# TIMESQUARE.net
KiCad netlist of a schematic drawn in EAGLE
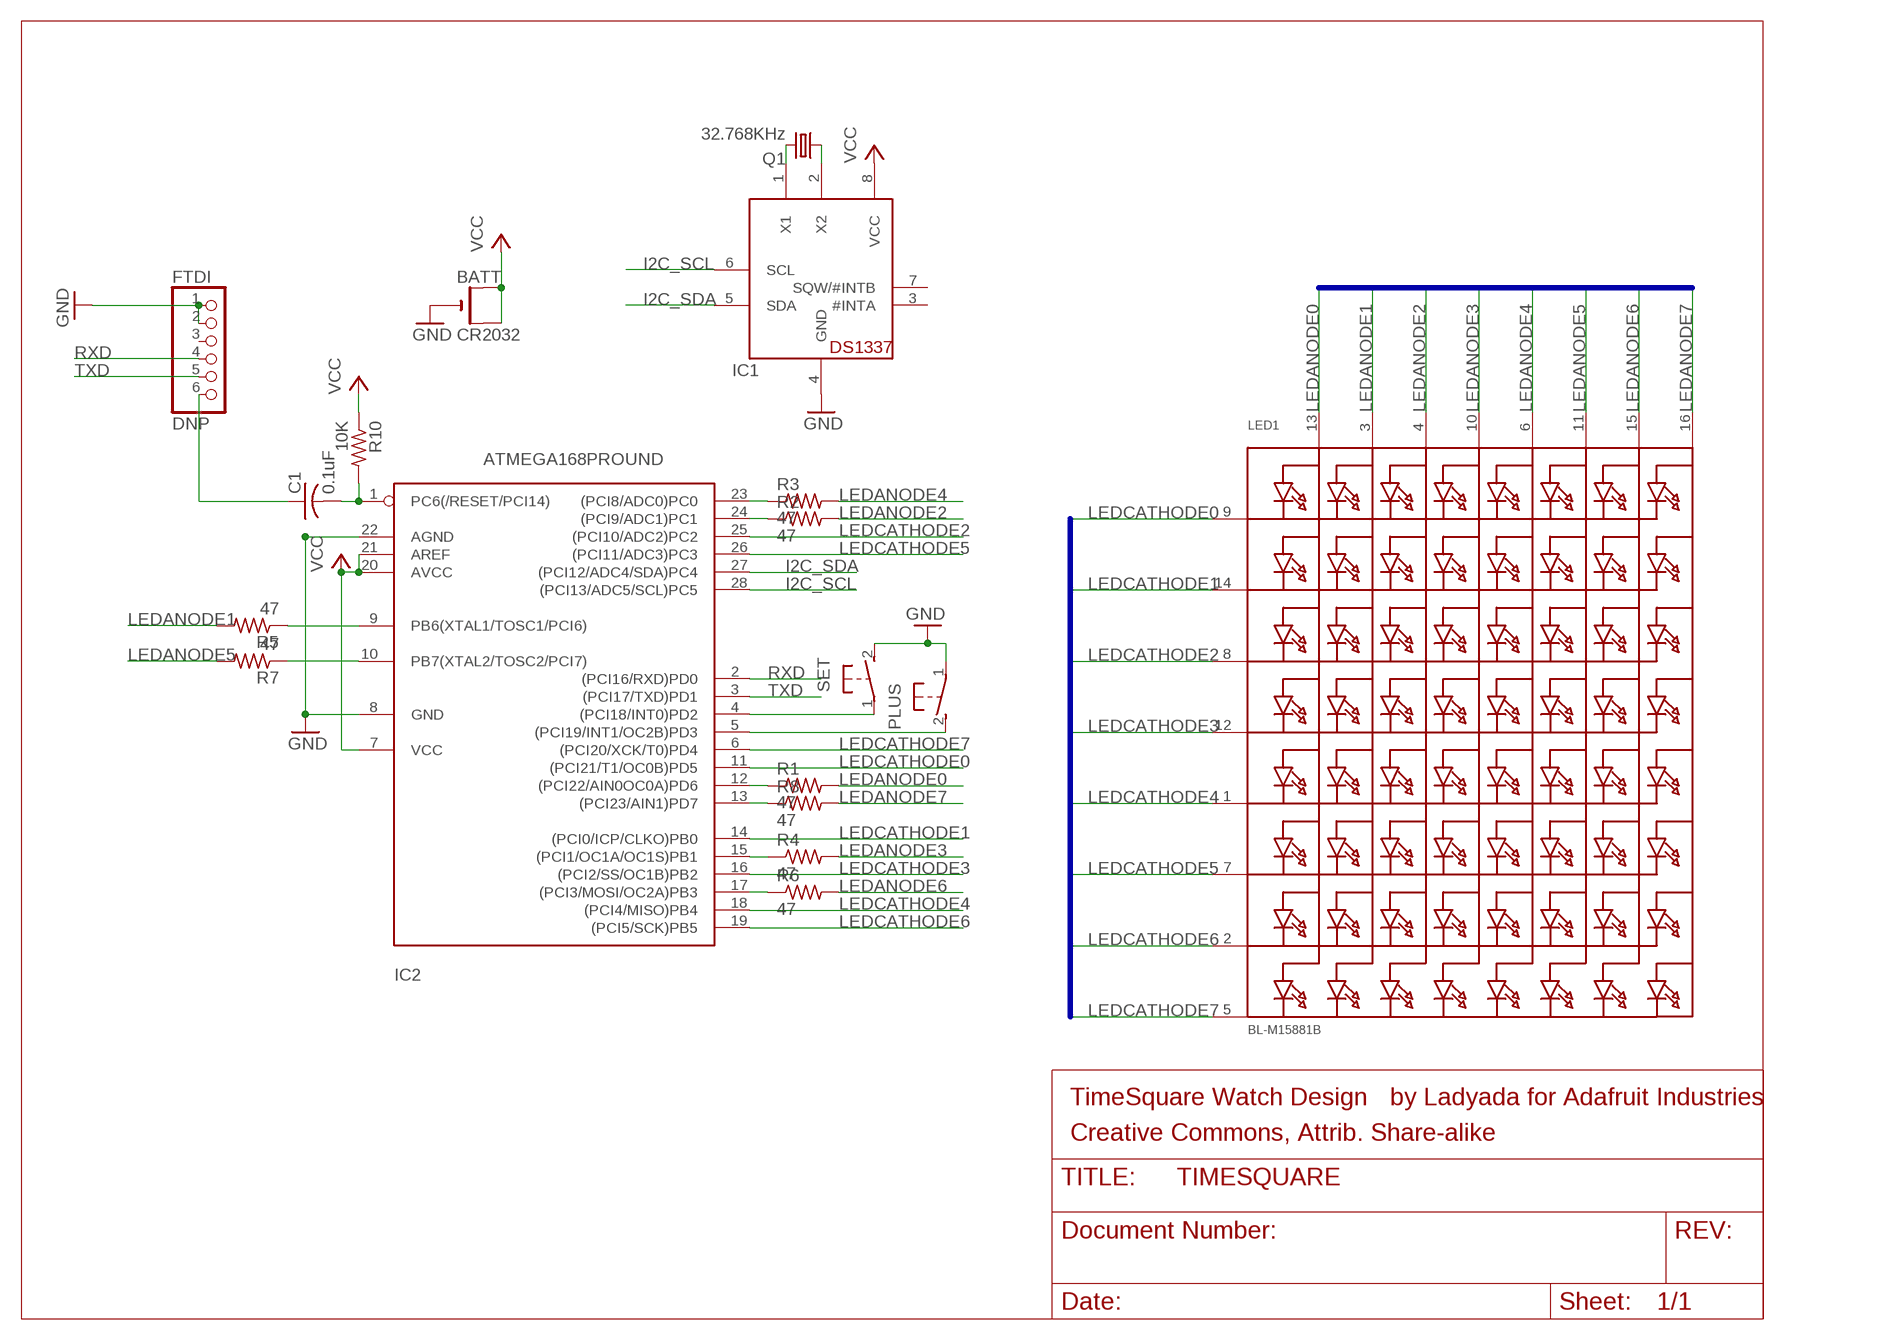
[diagram p0: schematic, sheet 1]

(export (version "E")
  (design (tool "Eeschema 10.0.6"))
  (components
    (comp (ref "BATT")
      (value "CR2032")
      (footprint "eagle-import:CR2032-THRU")
      (libsource (lib "eagle-import") (part "CR2032THM"))
    )
    (comp (ref "C1")
      (value "0.1uF")
      (footprint "eagle-import:C025-025X050")
      (libsource (lib "eagle-import") (part "C-US025-025X050"))
    )
    (comp (ref "FTDI")
      (value "DNP")
      (footprint "eagle-import:1X06-CLEAN")
      (libsource (lib "eagle-import") (part "PINHD-1X6CLEAN"))
    )
    (comp (ref "IC1")
      (value "DS1337")
      (footprint "eagle-import:DIL08-ROUND")
      (libsource (lib "eagle-import") (part "DS1337"))
    )
    (comp (ref "IC2")
      (value "ATMEGA168PROUND")
      (footprint "eagle-import:DIL28-3-ROUND")
      (libsource (lib "eagle-import") (part "ATMEGA168PROUND"))
    )
    (comp (ref "LED1")
      (value "BL-M15881B")
      (footprint "eagle-import:SEGMENT_BL-M15A881")
      (libsource (lib "eagle-import") (part "SEGMENT_8X8_ROWCATHODEBL-M15"))
    )
    (comp (ref "PLUS")
      (value "31-XXSKINNY")
      (footprint "eagle-import:B3F-31XX-SKINNIER")
      (libsource (lib "eagle-import") (part "31-XXSKINNY"))
    )
    (comp (ref "Q1")
      (value "32.768KHz")
      (footprint "eagle-import:TC38H")
      (libsource (lib "eagle-import") (part "CRYSTALTC38H"))
    )
    (comp (ref "R1")
      (value "47")
      (footprint "eagle-import:0204_7")
      (libsource (lib "eagle-import") (part "R-US_0204/7"))
    )
    (comp (ref "R2")
      (value "47")
      (footprint "eagle-import:0204_7")
      (libsource (lib "eagle-import") (part "R-US_0204/7"))
    )
    (comp (ref "R3")
      (value "47")
      (footprint "eagle-import:0204_7")
      (libsource (lib "eagle-import") (part "R-US_0204/7"))
    )
    (comp (ref "R4")
      (value "47")
      (footprint "eagle-import:0204_7")
      (libsource (lib "eagle-import") (part "R-US_0204/7"))
    )
    (comp (ref "R5")
      (value "47")
      (footprint "eagle-import:0204_7")
      (libsource (lib "eagle-import") (part "R-US_0204/7"))
    )
    (comp (ref "R6")
      (value "47")
      (footprint "eagle-import:0204_7")
      (libsource (lib "eagle-import") (part "R-US_0204/7"))
    )
    (comp (ref "R7")
      (value "47")
      (footprint "eagle-import:0204_7")
      (libsource (lib "eagle-import") (part "R-US_0204/7"))
    )
    (comp (ref "R8")
      (value "47")
      (footprint "eagle-import:0204_7")
      (libsource (lib "eagle-import") (part "R-US_0204/7"))
    )
    (comp (ref "R10")
      (value "10K")
      (footprint "eagle-import:0204_7")
      (libsource (lib "eagle-import") (part "R-US_0204/7"))
    )
    (comp (ref "SET")
      (value "31-XXSKINNY")
      (footprint "eagle-import:B3F-31XX-SKINNIER")
      (libsource (lib "eagle-import") (part "31-XXSKINNY"))
    )
  )
  (nets
    (net (code "1") (name "/I2C_SCL") (class "Default")
      (node (ref "IC1") (pin "6") (pinfunction "SCL_6") (pintype "bidirectional"))
      (node (ref "IC2") (pin "28") (pinfunction "(PCI13/ADC5/SCL)PC5_28") (pintype "bidirectional"))
    )
    (net (code "2") (name "/I2C_SDA") (class "Default")
      (node (ref "IC1") (pin "5") (pinfunction "SDA_5") (pintype "bidirectional"))
      (node (ref "IC2") (pin "27") (pinfunction "(PCI12/ADC4/SDA)PC4_27") (pintype "bidirectional"))
    )
    (net (code "3") (name "/LEDANODE0") (class "Default")
      (node (ref "LED1") (pin "13") (pinfunction "A1_13") (pintype "bidirectional"))
      (node (ref "R1") (pin "2") (pinfunction "2_2") (pintype "passive"))
    )
    (net (code "4") (name "/LEDANODE1") (class "Default")
      (node (ref "LED1") (pin "3") (pinfunction "A2_3") (pintype "bidirectional"))
      (node (ref "R5") (pin "2") (pinfunction "2_2") (pintype "passive"))
    )
    (net (code "5") (name "/LEDANODE2") (class "Default")
      (node (ref "LED1") (pin "4") (pinfunction "A3_4") (pintype "bidirectional"))
      (node (ref "R2") (pin "2") (pinfunction "2_2") (pintype "passive"))
    )
    (net (code "6") (name "/LEDANODE3") (class "Default")
      (node (ref "LED1") (pin "10") (pinfunction "A4_10") (pintype "bidirectional"))
      (node (ref "R4") (pin "2") (pinfunction "2_2") (pintype "passive"))
    )
    (net (code "7") (name "/LEDANODE4") (class "Default")
      (node (ref "LED1") (pin "6") (pinfunction "A5_6") (pintype "bidirectional"))
      (node (ref "R3") (pin "2") (pinfunction "2_2") (pintype "passive"))
    )
    (net (code "8") (name "/LEDANODE5") (class "Default")
      (node (ref "LED1") (pin "11") (pinfunction "A6_11") (pintype "bidirectional"))
      (node (ref "R7") (pin "2") (pinfunction "2_2") (pintype "passive"))
    )
    (net (code "9") (name "/LEDANODE6") (class "Default")
      (node (ref "LED1") (pin "15") (pinfunction "A7_15") (pintype "bidirectional"))
      (node (ref "R6") (pin "2") (pinfunction "2_2") (pintype "passive"))
    )
    (net (code "10") (name "/LEDANODE7") (class "Default")
      (node (ref "LED1") (pin "16") (pinfunction "A8_16") (pintype "bidirectional"))
      (node (ref "R8") (pin "2") (pinfunction "2_2") (pintype "passive"))
    )
    (net (code "11") (name "/LEDCATHODE0") (class "Default")
      (node (ref "IC2") (pin "11") (pinfunction "(PCI21/T1/OC0B)PD5_11") (pintype "bidirectional"))
      (node (ref "LED1") (pin "9") (pinfunction "K1_9") (pintype "bidirectional"))
    )
    (net (code "12") (name "/LEDCATHODE1") (class "Default")
      (node (ref "IC2") (pin "14") (pinfunction "(PCI0/ICP/CLKO)PB0_14") (pintype "bidirectional"))
      (node (ref "LED1") (pin "14") (pinfunction "K2_14") (pintype "bidirectional"))
    )
    (net (code "13") (name "/LEDCATHODE2") (class "Default")
      (node (ref "IC2") (pin "25") (pinfunction "(PCI10/ADC2)PC2_25") (pintype "bidirectional"))
      (node (ref "LED1") (pin "8") (pinfunction "K3_8") (pintype "bidirectional"))
    )
    (net (code "14") (name "/LEDCATHODE3") (class "Default")
      (node (ref "IC2") (pin "16") (pinfunction "(PCI2/SS/OC1B)PB2_16") (pintype "bidirectional"))
      (node (ref "LED1") (pin "12") (pinfunction "K4_12") (pintype "bidirectional"))
    )
    (net (code "15") (name "/LEDCATHODE4") (class "Default")
      (node (ref "IC2") (pin "18") (pinfunction "(PCI4/MISO)PB4_18") (pintype "bidirectional"))
      (node (ref "LED1") (pin "1") (pinfunction "K5_1") (pintype "bidirectional"))
    )
    (net (code "16") (name "/LEDCATHODE5") (class "Default")
      (node (ref "IC2") (pin "26") (pinfunction "(PCI11/ADC3)PC3_26") (pintype "bidirectional"))
      (node (ref "LED1") (pin "7") (pinfunction "K6_7") (pintype "bidirectional"))
    )
    (net (code "17") (name "/LEDCATHODE6") (class "Default")
      (node (ref "IC2") (pin "19") (pinfunction "(PCI5/SCK)PB5_19") (pintype "bidirectional"))
      (node (ref "LED1") (pin "2") (pinfunction "K7_2") (pintype "bidirectional"))
    )
    (net (code "18") (name "/LEDCATHODE7") (class "Default")
      (node (ref "IC2") (pin "6") (pinfunction "(PCI20/XCK/T0)PD4_6") (pintype "bidirectional"))
      (node (ref "LED1") (pin "5") (pinfunction "K8_5") (pintype "bidirectional"))
    )
    (net (code "19") (name "/RXD") (class "Default")
      (node (ref "FTDI") (pin "4") (pinfunction "4_4") (pintype "passive"))
      (node (ref "IC2") (pin "2") (pinfunction "(PCI16/RXD)PD0_2") (pintype "bidirectional"))
    )
    (net (code "20") (name "/TXD") (class "Default")
      (node (ref "FTDI") (pin "5") (pinfunction "5_5") (pintype "passive"))
      (node (ref "IC2") (pin "3") (pinfunction "(PCI17/TXD)PD1_3") (pintype "bidirectional"))
    )
    (net (code "21") (name "GND") (class "Default")
      (node (ref "BATT") (pin "-") (pinfunction "-_-") (pintype "passive"))
      (node (ref "FTDI") (pin "1") (pinfunction "1_1") (pintype "passive"))
      (node (ref "FTDI") (pin "2") (pinfunction "2_2") (pintype "passive"))
      (node (ref "IC1") (pin "4") (pinfunction "GND_4") (pintype "power_in"))
      (node (ref "IC2") (pin "22") (pinfunction "AGND_22") (pintype "bidirectional"))
      (node (ref "IC2") (pin "8") (pinfunction "GND_8") (pintype "bidirectional"))
      (node (ref "PLUS") (pin "1") (pinfunction "P_1") (pintype "passive"))
      (node (ref "SET") (pin "2") (pinfunction "S_2") (pintype "passive"))
    )
    (net (code "22") (name "Net-(C1-Pad1)") (class "Default")
      (node (ref "C1") (pin "1") (pinfunction "1_1") (pintype "passive"))
      (node (ref "FTDI") (pin "6") (pinfunction "6_6") (pintype "passive"))
    )
    (net (code "23") (name "Net-(IC1-X1)") (class "Default")
      (node (ref "IC1") (pin "1") (pinfunction "X1_1") (pintype "passive"))
      (node (ref "Q1") (pin "2") (pinfunction "2_2") (pintype "passive"))
    )
    (net (code "24") (name "Net-(IC1-X2)") (class "Default")
      (node (ref "IC1") (pin "2") (pinfunction "X2_2") (pintype "passive"))
      (node (ref "Q1") (pin "1") (pinfunction "1_1") (pintype "passive"))
    )
    (net (code "25") (name "Net-(IC2-(PCI1{slash}OC1A{slash}OC1S)PB1)") (class "Default")
      (node (ref "IC2") (pin "15") (pinfunction "(PCI1/OC1A/OC1S)PB1_15") (pintype "bidirectional"))
      (node (ref "R4") (pin "1") (pinfunction "1_1") (pintype "passive"))
    )
    (net (code "26") (name "Net-(IC2-(PCI3{slash}MOSI{slash}OC2A)PB3)") (class "Default")
      (node (ref "IC2") (pin "17") (pinfunction "(PCI3/MOSI/OC2A)PB3_17") (pintype "bidirectional"))
      (node (ref "R6") (pin "1") (pinfunction "1_1") (pintype "passive"))
    )
    (net (code "27") (name "Net-(IC2-(PCI8{slash}ADC0)PC0)") (class "Default")
      (node (ref "IC2") (pin "23") (pinfunction "(PCI8/ADC0)PC0_23") (pintype "bidirectional"))
      (node (ref "R3") (pin "1") (pinfunction "1_1") (pintype "passive"))
    )
    (net (code "28") (name "Net-(IC2-(PCI9{slash}ADC1)PC1)") (class "Default")
      (node (ref "IC2") (pin "24") (pinfunction "(PCI9/ADC1)PC1_24") (pintype "bidirectional"))
      (node (ref "R2") (pin "1") (pinfunction "1_1") (pintype "passive"))
    )
    (net (code "29") (name "Net-(IC2-(PCI18{slash}INT0)PD2)") (class "Default")
      (node (ref "IC2") (pin "4") (pinfunction "(PCI18/INT0)PD2_4") (pintype "bidirectional"))
      (node (ref "SET") (pin "1") (pinfunction "P_1") (pintype "passive"))
    )
    (net (code "30") (name "Net-(IC2-(PCI19{slash}INT1{slash}OC2B)PD3)") (class "Default")
      (node (ref "IC2") (pin "5") (pinfunction "(PCI19/INT1/OC2B)PD3_5") (pintype "bidirectional"))
      (node (ref "PLUS") (pin "2") (pinfunction "S_2") (pintype "passive"))
    )
    (net (code "31") (name "Net-(IC2-(PCI22{slash}AIN0OC0A)PD6)") (class "Default")
      (node (ref "IC2") (pin "12") (pinfunction "(PCI22/AIN0OC0A)PD6_12") (pintype "bidirectional"))
      (node (ref "R1") (pin "1") (pinfunction "1_1") (pintype "passive"))
    )
    (net (code "32") (name "Net-(IC2-(PCI23{slash}AIN1)PD7)") (class "Default")
      (node (ref "IC2") (pin "13") (pinfunction "(PCI23/AIN1)PD7_13") (pintype "bidirectional"))
      (node (ref "R8") (pin "1") (pinfunction "1_1") (pintype "passive"))
    )
    (net (code "33") (name "Net-(IC2-PB6(XTAL1{slash}TOSC1{slash}PCI6))") (class "Default")
      (node (ref "IC2") (pin "9") (pinfunction "PB6(XTAL1/TOSC1/PCI6)_9") (pintype "bidirectional"))
      (node (ref "R5") (pin "1") (pinfunction "1_1") (pintype "passive"))
    )
    (net (code "34") (name "Net-(IC2-PB7(XTAL2{slash}TOSC2{slash}PCI7))") (class "Default")
      (node (ref "IC2") (pin "10") (pinfunction "PB7(XTAL2/TOSC2/PCI7)_10") (pintype "bidirectional"))
      (node (ref "R7") (pin "1") (pinfunction "1_1") (pintype "passive"))
    )
    (net (code "35") (name "Net-(IC2-PC6({slash}RESET{slash}PCI14))") (class "Default")
      (node (ref "C1") (pin "2") (pinfunction "2_2") (pintype "passive"))
      (node (ref "IC2") (pin "1") (pinfunction "PC6(/RESET/PCI14)_1") (pintype "bidirectional"))
      (node (ref "R10") (pin "2") (pinfunction "2_2") (pintype "passive"))
    )
    (net (code "36") (name "VCC") (class "Default")
      (node (ref "BATT") (pin "+1") (pinfunction "+_+1") (pintype "passive"))
      (node (ref "BATT") (pin "+2") (pinfunction "+1_+2") (pintype "passive"))
      (node (ref "IC1") (pin "8") (pinfunction "VCC_8") (pintype "power_in"))
      (node (ref "IC2") (pin "20") (pinfunction "AVCC_20") (pintype "bidirectional"))
      (node (ref "IC2") (pin "21") (pinfunction "AREF_21") (pintype "bidirectional"))
      (node (ref "IC2") (pin "7") (pinfunction "VCC_7") (pintype "bidirectional"))
      (node (ref "R10") (pin "1") (pinfunction "1_1") (pintype "passive"))
    )
    (net (code "37") (name "unconnected-(FTDI-Pad3)") (class "Default")
      (node (ref "FTDI") (pin "3") (pinfunction "3_3") (pintype "passive"))
    )
    (net (code "38") (name "unconnected-(IC1-#INTA-Pad3)") (class "Default")
      (node (ref "IC1") (pin "3") (pinfunction "#INTA_3") (pintype "output"))
    )
    (net (code "39") (name "unconnected-(IC1-SQW{slash}#INTB-Pad7)") (class "Default")
      (node (ref "IC1") (pin "7") (pinfunction "SQW/#INTB_7") (pintype "output"))
    )
  )
)
